# 93LC56BT_128x16BIT.net
KiCad netlist of a schematic drawn in Altium Designer
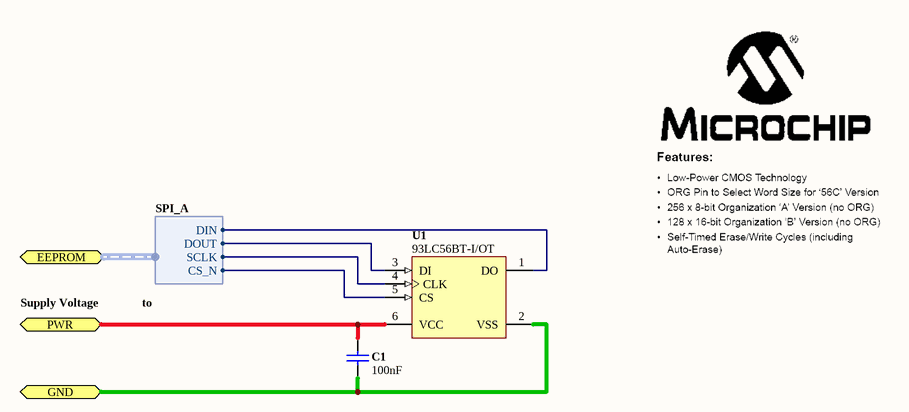
[diagram p0: 93LC56BT_128x16BIT.SchDoc]

(export (version "E")
  (design (tool "Eeschema 10.0.6"))
  (components
    (comp (ref "C1")
      (value "100nF")
      (footprint "CAPC0402(1005)60_N")
      (description "CAP 100nF 10V ±10% 0402 (1005 Metric) Thickness 0.6mm SMD")
      (fields (field (name "TOLERANCE") "±10%") (field (name "Comment") "CAP 100nF 10V 0402(1005)"))
      (libsource (lib "Altium Vault") (part "CMP-1034-02065-1"))
    )
    (comp (ref "U1")
      (value "93LC56BT-I/OT")
      (footprint "SOT-23-OT6_N")
      (description "2K, 128x16-bit, 2.5V Microwire Serial EEPROM, 6-Pin SOT-23, Industrial Temperature, Tape and Reel")
      (libsource (lib "Altium Vault") (part "CMP-0162-00356-1"))
    )
  )
  (nets
    (net (code "2") (name "/CS_N") (class "Default")
      (node (ref "U1") (pin "5") (pinfunction "CS_5") (pintype "input"))
    )
    (net (code "3") (name "/DIN") (class "Default")
      (node (ref "U1") (pin "1") (pinfunction "DO_1") (pintype "tri_state"))
    )
    (net (code "4") (name "/DOUT") (class "Default")
      (node (ref "U1") (pin "3") (pinfunction "DI_3") (pintype "input"))
    )
    (net (code "5") (name "/GND") (class "Default")
      (node (ref "C1") (pin "2") (pinfunction "2_2") (pintype "passive"))
      (node (ref "U1") (pin "2") (pinfunction "VSS_2") (pintype "power_in"))
    )
    (net (code "6") (name "/PWR") (class "Default")
      (node (ref "C1") (pin "1") (pinfunction "1_1") (pintype "passive"))
      (node (ref "U1") (pin "6") (pinfunction "VCC_6") (pintype "power_in"))
    )
    (net (code "7") (name "/SCLK") (class "Default")
      (node (ref "U1") (pin "4") (pinfunction "CLK_4") (pintype "input"))
    )
  )
)
